# revision.net
KiCad netlist of a schematic drawn in EAGLE
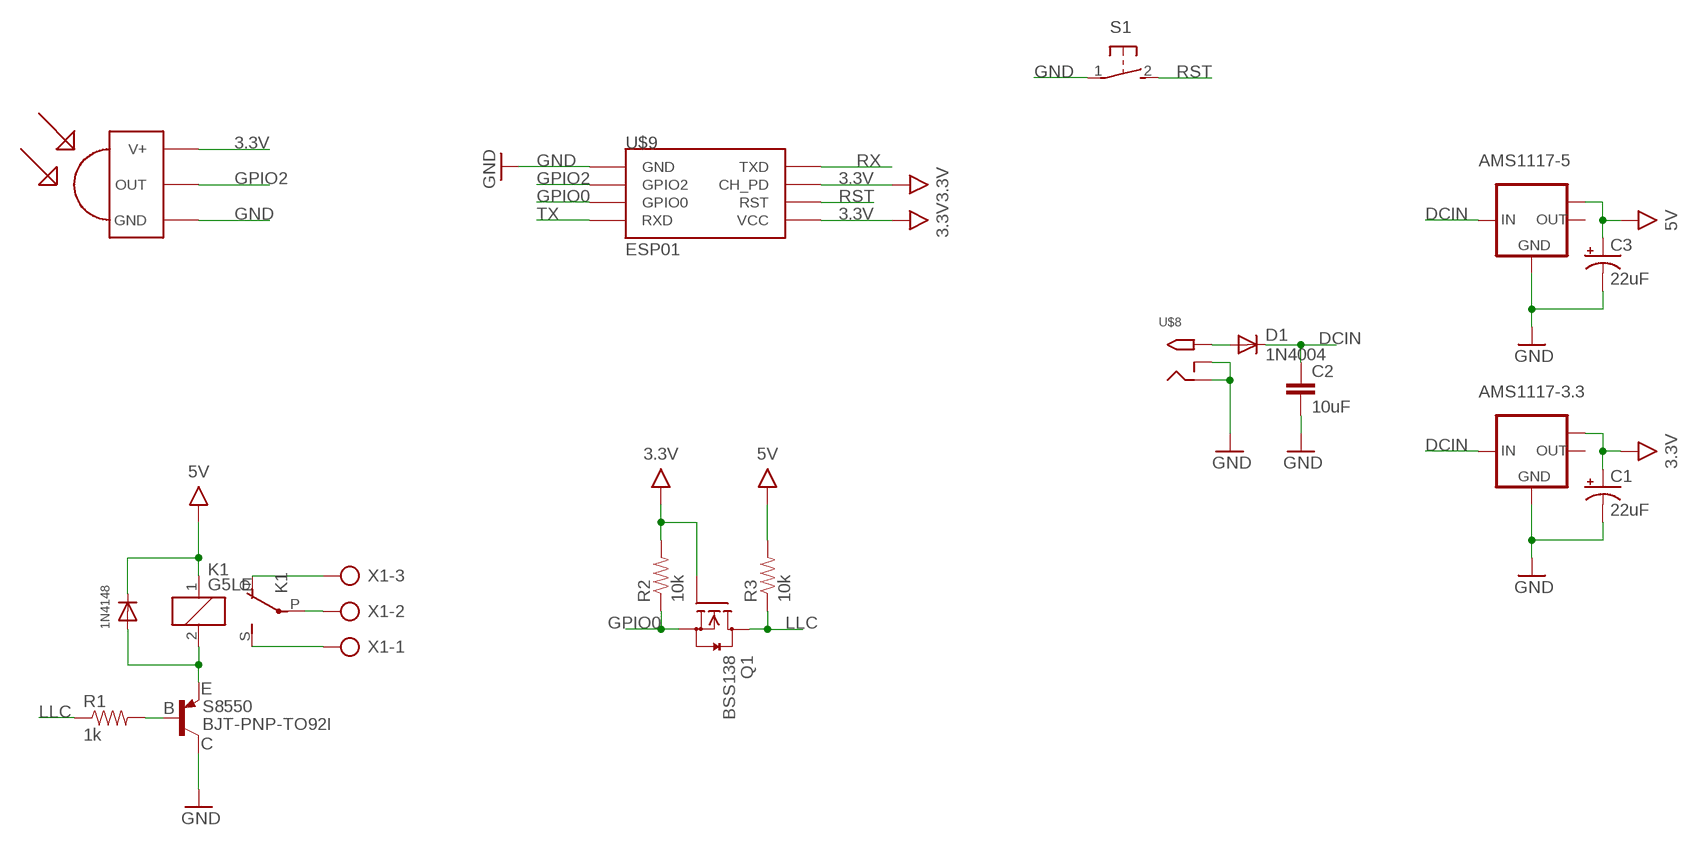
[diagram p0: schematic, sheet 1]

(export (version "E")
  (design (tool "Eeschema 10.0.6"))
  (components
    (comp (ref "1N4148")
      (value "DIODESOD-123")
      (footprint "eagle-import:SOD-123")
      (libsource (lib "eagle-import") (part "DIODESOD-123"))
    )
    (comp (ref "AMS1117-3.3")
      (value "LM1117MPX-3.3")
      (footprint "eagle-import:SOT223")
      (libsource (lib "eagle-import") (part "LM1117MPX-3.3"))
    )
    (comp (ref "AMS1117-5")
      (value "LM1117MPX-3.3")
      (footprint "eagle-import:SOT223")
      (libsource (lib "eagle-import") (part "LM1117MPX-3.3"))
    )
    (comp (ref "C1")
      (value "22uF")
      (footprint "eagle-import:EIA3216-KIT")
      (libsource (lib "eagle-import") (part "CAP_POL1206-KIT"))
    )
    (comp (ref "C2")
      (value "10uF")
      (footprint "eagle-import:0805")
      (libsource (lib "eagle-import") (part "CAP0805"))
    )
    (comp (ref "C3")
      (value "22uF")
      (footprint "eagle-import:EIA3216-KIT")
      (libsource (lib "eagle-import") (part "CAP_POL1206-KIT"))
    )
    (comp (ref "D1")
      (value "1N4004")
      (footprint "eagle-import:DO41-10")
      (libsource (lib "eagle-import") (part "1N4004"))
    )
    (comp (ref "K1")
      (value "G5LE")
      (footprint "eagle-import:G5LE")
      (libsource (lib "eagle-import") (part "G5LE"))
    )
    (comp (ref "Q1")
      (value "BSS138")
      (footprint "eagle-import:SOT23")
      (libsource (lib "eagle-import") (part "BSS138"))
    )
    (comp (ref "R1")
      (value "1k")
      (footprint "eagle-import:0805")
      (libsource (lib "eagle-import") (part "RESISTOR0805-RES"))
    )
    (comp (ref "R2")
      (value "10k")
      (footprint "eagle-import:0805")
      (libsource (lib "eagle-import") (part "RESISTOR0805-RES"))
    )
    (comp (ref "R3")
      (value "10k")
      (footprint "eagle-import:0805")
      (libsource (lib "eagle-import") (part "RESISTOR0805-RES"))
    )
    (comp (ref "S1")
      (value "31-XX")
      (footprint "eagle-import:B3F-31XX")
      (fields (field (name "MPN") "B3F-3100"))
      (libsource (lib "eagle-import") (part "31-XX"))
    )
    (comp (ref "S8550")
      (value "BJT-PNP-TO92I")
      (footprint "eagle-import:TO92I")
      (libsource (lib "eagle-import") (part "BJT-PNP-TO92I"))
    )
    (comp (ref "U$8")
      (value "2.1MMJACKTHM")
      (footprint "eagle-import:PJ-102A")
      (libsource (lib "eagle-import") (part "2.1MMJACKTHM"))
    )
    (comp (ref "U$9")
      (value "ESP01")
      (footprint "eagle-import:ESP01")
      (libsource (lib "eagle-import") (part "ESP01"))
    )
    (comp (ref "U$10")
      (value "TSOP1736")
      (footprint "eagle-import:TSOP17XX")
      (libsource (lib "eagle-import") (part "TSOP1736"))
    )
    (comp (ref "X1")
      (value "AK300/3")
      (footprint "eagle-import:AK300_3")
      (libsource (lib "eagle-import") (part "AK300/3"))
    )
  )
  (nets
    (net (code "1") (name "/DCIN") (class "Default")
      (node (ref "AMS1117-3.3") (pin "3") (pinfunction "IN_3") (pintype "input"))
      (node (ref "AMS1117-5") (pin "3") (pinfunction "IN_3") (pintype "input"))
      (node (ref "C2") (pin "1") (pinfunction "1_1") (pintype "passive"))
      (node (ref "D1") (pin "C") (pinfunction "C_C") (pintype "passive"))
    )
    (net (code "2") (name "/GPIO0") (class "Default")
      (node (ref "Q1") (pin "2") (pinfunction "S_2") (pintype "passive"))
      (node (ref "R2") (pin "1") (pinfunction "1_1") (pintype "passive"))
      (node (ref "U$9") (pin "GPIO0") (pinfunction "GPIO0_GPIO0") (pintype "bidirectional"))
    )
    (net (code "3") (name "/GPIO2") (class "Default")
      (node (ref "U$10") (pin "OUT") (pinfunction "OUT_OUT") (pintype "bidirectional"))
      (node (ref "U$9") (pin "GPIO2") (pinfunction "GPIO2_GPIO2") (pintype "bidirectional"))
    )
    (net (code "4") (name "/LLC") (class "Default")
      (node (ref "Q1") (pin "3") (pinfunction "D_3") (pintype "passive"))
      (node (ref "R1") (pin "1") (pinfunction "1_1") (pintype "passive"))
      (node (ref "R3") (pin "1") (pinfunction "1_1") (pintype "passive"))
    )
    (net (code "5") (name "/RST") (class "Default")
      (node (ref "S1") (pin "2") (pinfunction "S_2") (pintype "passive"))
      (node (ref "U$9") (pin "RST") (pinfunction "RST_RST") (pintype "bidirectional"))
    )
    (net (code "6") (name "/RX") (class "Default")
      (node (ref "U$9") (pin "TX") (pinfunction "TXD_TX") (pintype "bidirectional"))
    )
    (net (code "7") (name "/TX") (class "Default")
      (node (ref "U$9") (pin "RX") (pinfunction "RXD_RX") (pintype "bidirectional"))
    )
    (net (code "8") (name "3.3V") (class "Default")
      (node (ref "AMS1117-3.3") (pin "TAB") (pinfunction "OUT1_TAB") (pintype "passive"))
      (node (ref "C1") (pin "A") (pinfunction "+_A") (pintype "passive"))
      (node (ref "Q1") (pin "1") (pinfunction "G_1") (pintype "passive"))
      (node (ref "R2") (pin "2") (pinfunction "2_2") (pintype "passive"))
      (node (ref "U$10") (pin "V+") (pinfunction "V+_V+") (pintype "bidirectional"))
      (node (ref "U$9") (pin "CH_PD") (pinfunction "CH_PD_CH_PD") (pintype "bidirectional"))
      (node (ref "U$9") (pin "VCC") (pinfunction "VCC_VCC") (pintype "bidirectional"))
    )
    (net (code "9") (name "5V") (class "Default")
      (node (ref "1N4148") (pin "C") (pinfunction "C_C") (pintype "passive"))
      (node (ref "AMS1117-5") (pin "TAB") (pinfunction "OUT1_TAB") (pintype "passive"))
      (node (ref "C3") (pin "A") (pinfunction "+_A") (pintype "passive"))
      (node (ref "K1") (pin "1") (pinfunction "1_1") (pintype "passive"))
      (node (ref "R3") (pin "2") (pinfunction "2_2") (pintype "passive"))
    )
    (net (code "10") (name "GND") (class "Default")
      (node (ref "AMS1117-3.3") (pin "1") (pinfunction "GND_1") (pintype "input"))
      (node (ref "AMS1117-5") (pin "1") (pinfunction "GND_1") (pintype "input"))
      (node (ref "C1") (pin "C") (pinfunction "-_C") (pintype "passive"))
      (node (ref "C2") (pin "2") (pinfunction "2_2") (pintype "passive"))
      (node (ref "C3") (pin "C") (pinfunction "-_C") (pintype "passive"))
      (node (ref "S1") (pin "1") (pinfunction "P_1") (pintype "passive"))
      (node (ref "S8550") (pin "C") (pinfunction "C_C") (pintype "passive"))
      (node (ref "U$10") (pin "GND") (pinfunction "GND_GND") (pintype "bidirectional"))
      (node (ref "U$8") (pin "RING") (pinfunction "RING_RING") (pintype "bidirectional"))
      (node (ref "U$8") (pin "RING_SW") (pinfunction "RING_SW_RING_SW") (pintype "bidirectional"))
      (node (ref "U$9") (pin "GND") (pinfunction "GND_GND") (pintype "bidirectional"))
    )
    (net (code "11") (name "Net-(1N4148-PadA)") (class "Default")
      (node (ref "1N4148") (pin "A") (pinfunction "A_A") (pintype "passive"))
      (node (ref "K1") (pin "2") (pinfunction "2_2") (pintype "passive"))
      (node (ref "S8550") (pin "E") (pinfunction "E_E") (pintype "passive"))
    )
    (net (code "12") (name "Net-(D1-PadA)") (class "Default")
      (node (ref "D1") (pin "A") (pinfunction "A_A") (pintype "passive"))
      (node (ref "U$8") (pin "TIP") (pinfunction "TIP_TIP") (pintype "bidirectional"))
    )
    (net (code "13") (name "Net-(R1-Pad2)") (class "Default")
      (node (ref "R1") (pin "2") (pinfunction "2_2") (pintype "passive"))
      (node (ref "S8550") (pin "B") (pinfunction "B_B") (pintype "passive"))
    )
    (net (code "14") (name "Net-(X1A-KL)") (class "Default")
      (node (ref "K1") (pin "S") (pinfunction "S_S") (pintype "passive"))
      (node (ref "X1") (pin "1") (pinfunction "KL_1") (pintype "passive"))
    )
    (net (code "15") (name "Net-(X1B-KL)") (class "Default")
      (node (ref "K1") (pin "P") (pinfunction "P_P") (pintype "passive"))
      (node (ref "X1") (pin "2") (pinfunction "KL_2") (pintype "passive"))
    )
    (net (code "16") (name "Net-(X1C-KL)") (class "Default")
      (node (ref "K1") (pin "O") (pinfunction "O_O") (pintype "passive"))
      (node (ref "X1") (pin "3") (pinfunction "KL_3") (pintype "passive"))
    )
    (net (code "17") (name "unconnected-(AMS1117-3.3-OUT-Pad2)") (class "Default")
      (node (ref "AMS1117-3.3") (pin "2") (pinfunction "OUT_2") (pintype "passive"))
    )
    (net (code "18") (name "unconnected-(AMS1117-5-OUT-Pad2)") (class "Default")
      (node (ref "AMS1117-5") (pin "2") (pinfunction "OUT_2") (pintype "passive"))
    )
  )
)
